# Motor-Z.net
KiCad netlist of a schematic drawn in Altium Designer
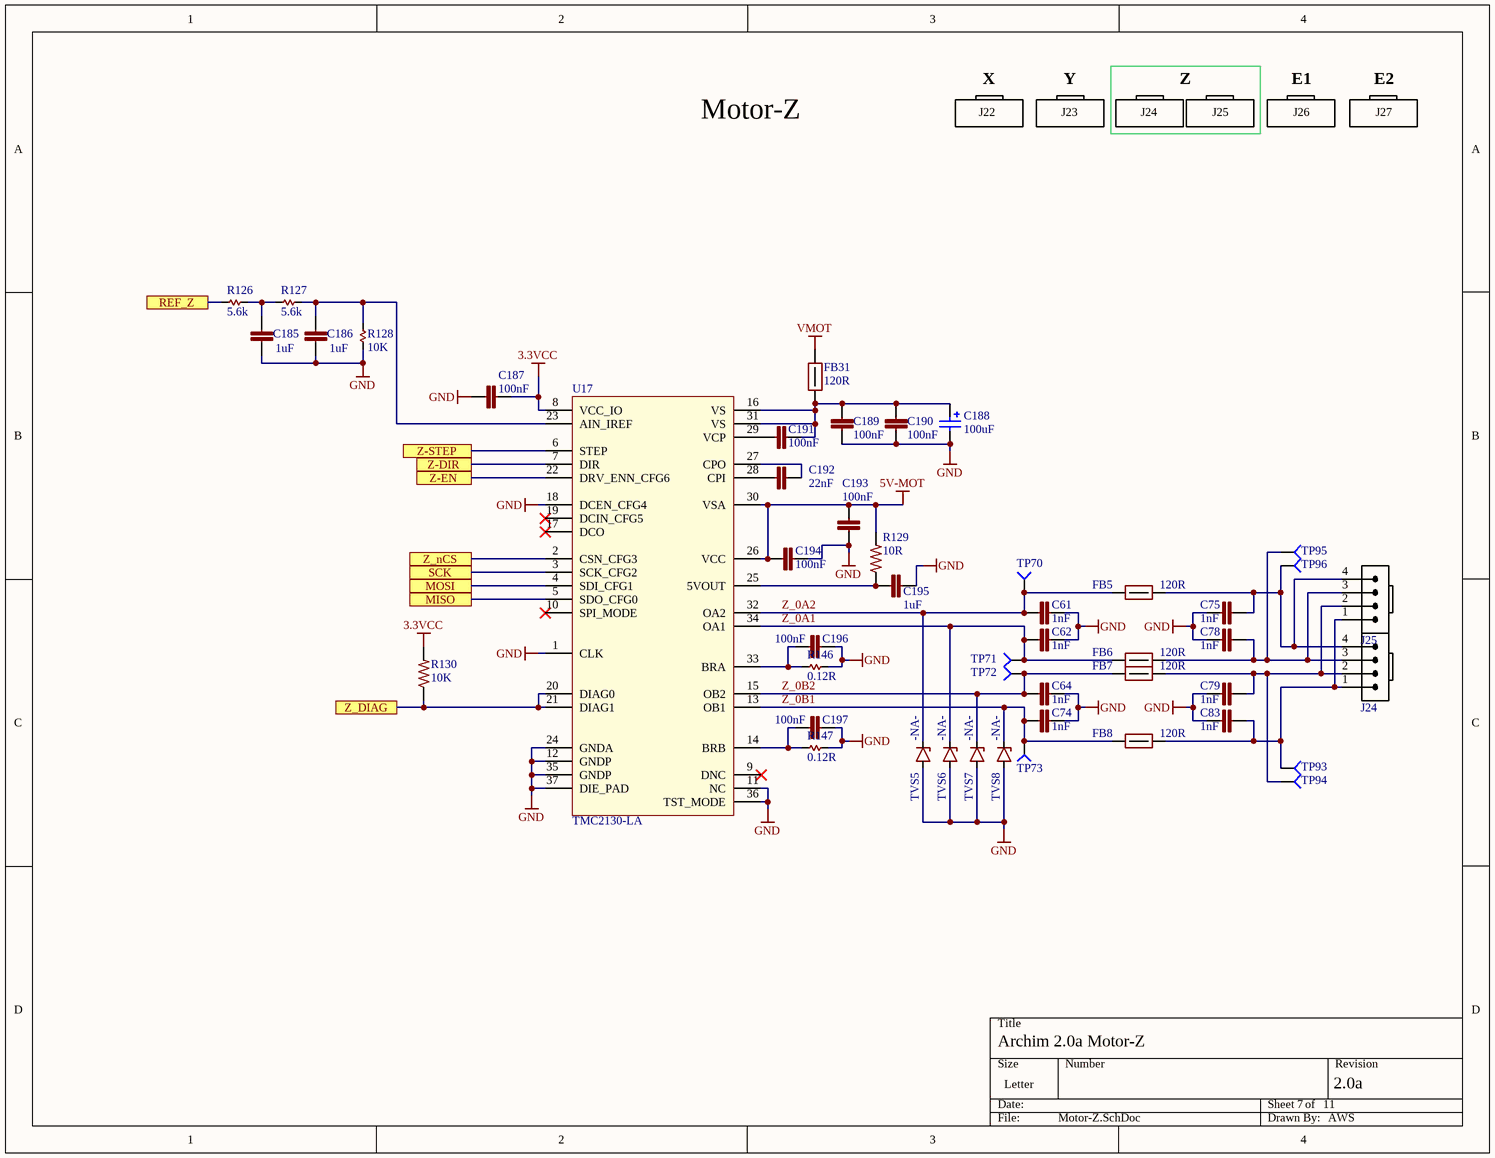
[diagram p0: Motor-Z.SchDoc]

(export (version "E")
  (design (tool "Eeschema 10.0.6"))
  (components
    (comp (ref "C61")
      (value "1nF")
      (footprint "C0402")
      (description "1000pF 50V Ceramic Capacitor X7R 0402 (1005 Metric) 0.039\" L x 0.020\" W (1.00mm x 0.50mm)")
      (fields (field (name "MANUFACTURER") "Murata") (field (name "PART") "1nF 50V X7R 0402"))
      (libsource (lib "3Delight") (part "CAP 1nF 50V 0402 X7R"))
    )
    (comp (ref "C62")
      (value "1nF")
      (footprint "C0402")
      (description "1000pF 50V Ceramic Capacitor X7R 0402 (1005 Metric) 0.039\" L x 0.020\" W (1.00mm x 0.50mm)")
      (fields (field (name "MANUFACTURER") "Murata") (field (name "PART") "1nF 50V X7R 0402"))
      (libsource (lib "3Delight") (part "CAP 1nF 50V 0402 X7R"))
    )
    (comp (ref "C64")
      (value "1nF")
      (footprint "C0402")
      (description "1000pF 50V Ceramic Capacitor X7R 0402 (1005 Metric) 0.039\" L x 0.020\" W (1.00mm x 0.50mm)")
      (fields (field (name "MANUFACTURER") "Murata") (field (name "PART") "1nF 50V X7R 0402"))
      (libsource (lib "3Delight") (part "CAP 1nF 50V 0402 X7R"))
    )
    (comp (ref "C74")
      (value "1nF")
      (footprint "C0402")
      (description "1000pF 50V Ceramic Capacitor X7R 0402 (1005 Metric) 0.039\" L x 0.020\" W (1.00mm x 0.50mm)")
      (fields (field (name "MANUFACTURER") "Murata") (field (name "PART") "1nF 50V X7R 0402"))
      (libsource (lib "3Delight") (part "CAP 1nF 50V 0402 X7R"))
    )
    (comp (ref "C75")
      (value "1nF")
      (footprint "C0402")
      (description "1000pF 50V Ceramic Capacitor X7R 0402 (1005 Metric) 0.039\" L x 0.020\" W (1.00mm x 0.50mm)")
      (fields (field (name "MANUFACTURER") "Murata") (field (name "PART") "1nF 50V X7R 0402"))
      (libsource (lib "3Delight") (part "CAP 1nF 50V 0402 X7R"))
    )
    (comp (ref "C78")
      (value "1nF")
      (footprint "C0402")
      (description "1000pF 50V Ceramic Capacitor X7R 0402 (1005 Metric) 0.039\" L x 0.020\" W (1.00mm x 0.50mm)")
      (fields (field (name "MANUFACTURER") "Murata") (field (name "PART") "1nF 50V X7R 0402"))
      (libsource (lib "3Delight") (part "CAP 1nF 50V 0402 X7R"))
    )
    (comp (ref "C79")
      (value "1nF")
      (footprint "C0402")
      (description "1000pF 50V Ceramic Capacitor X7R 0402 (1005 Metric) 0.039\" L x 0.020\" W (1.00mm x 0.50mm)")
      (fields (field (name "MANUFACTURER") "Murata") (field (name "PART") "1nF 50V X7R 0402"))
      (libsource (lib "3Delight") (part "CAP 1nF 50V 0402 X7R"))
    )
    (comp (ref "C83")
      (value "1nF")
      (footprint "C0402")
      (description "1000pF 50V Ceramic Capacitor X7R 0402 (1005 Metric) 0.039\" L x 0.020\" W (1.00mm x 0.50mm)")
      (fields (field (name "MANUFACTURER") "Murata") (field (name "PART") "1nF 50V X7R 0402"))
      (libsource (lib "3Delight") (part "CAP 1nF 50V 0402 X7R"))
    )
    (comp (ref "C185")
      (value "1uF")
      (footprint "C0402")
      (description "CAP CER 0402 1uF 6.3V 10% X5R")
      (fields (field (name "MANUFACTURER") "Murata") (field (name "PART") "1uF 6.3V X5R 0402"))
      (libsource (lib "") (part "GRM155R60J105KE19D_1"))
    )
    (comp (ref "C186")
      (value "1uF")
      (footprint "C0402")
      (description "CAP CER 0402 1uF 6.3V 10% X5R")
      (fields (field (name "MANUFACTURER") "Murata") (field (name "PART") "1uF 6.3V X5R 0402"))
      (libsource (lib "") (part "GRM155R60J105KE19D_1"))
    )
    (comp (ref "C187")
      (value "100nF")
      (footprint "C0402")
      (description "CAP CER 0402 100nF 16V 10% X7R")
      (fields (field (name "MANUFACTURER") "Murata") (field (name "PART") "0.1uF 16V X7R 0402"))
      (libsource (lib "") (part "GRM155R71C104KA88D_1"))
    )
    (comp (ref "C188")
      (value "100uF")
      (footprint "CAP-ELEC-063063077")
      (description "CAP ALUM 100UF 35V 20% SMD")
      (fields (field (name "MANUFACTURER") "Nichicon") (field (name "PART") "100uF 35V SMD Al-El"))
      (libsource (lib "3Delight") (part "UWT1V101MCL1GS"))
    )
    (comp (ref "C189")
      (value "100nF")
      (footprint "C0603")
      (description "CAP CER 0603 100nF 50V 10% X7R")
      (fields (field (name "MANUFACTURER") "Kemet") (field (name "PART") "100nF 50V X7R 0603"))
      (libsource (lib "") (part "C0603C104K5RACTU_2"))
    )
    (comp (ref "C190")
      (value "100nF")
      (footprint "C0603")
      (description "CAP CER 0603 100nF 50V 10% X7R")
      (fields (field (name "MANUFACTURER") "Kemet") (field (name "PART") "100nF 50V X7R 0603"))
      (libsource (lib "") (part "C0603C104K5RACTU_2"))
    )
    (comp (ref "C191")
      (value "100nF")
      (footprint "C0603")
      (description "CAP CER 0603 100nF 50V 10% X7R")
      (fields (field (name "MANUFACTURER") "Kemet") (field (name "PART") "100nF 50V X7R 0603"))
      (libsource (lib "") (part "C0603C104K5RACTU_1"))
    )
    (comp (ref "C192")
      (value "22nF")
      (footprint "C0402")
      (description "CAP CER 0402 22nF ±10% 50V X7R")
      (fields (field (name "MANUFACTURER") "YAGEO") (field (name "TOLERANCE") "+/- 10%"))
      (libsource (lib "3Delight") (part "GCM155R71H223KA55D"))
    )
    (comp (ref "C193")
      (value "100nF")
      (footprint "C0402")
      (description "CAP CER 0402 100nF 16V 10% X7R")
      (fields (field (name "MANUFACTURER") "Murata") (field (name "PART") "0.1uF 16V X7R 0402"))
      (libsource (lib "3Delight") (part "GRM155R71C104KA88D"))
    )
    (comp (ref "C194")
      (value "100nF")
      (footprint "C0402")
      (description "CAP CER 0402 100nF 16V 10% X7R")
      (fields (field (name "MANUFACTURER") "Murata") (field (name "PART") "0.1uF 16V X7R 0402"))
      (libsource (lib "") (part "GRM155R71C104KA88D_1"))
    )
    (comp (ref "C195")
      (value "1uF")
      (footprint "C0402")
      (description "CAP CER 0402 1uF 6.3V 10% X5R")
      (fields (field (name "MANUFACTURER") "Murata") (field (name "PART") "1uF 6.3V X5R 0402"))
      (libsource (lib "3Delight") (part "GRM155R60J105KE19D"))
    )
    (comp (ref "C196")
      (value "100nF")
      (footprint "C0603")
      (description "CAP CER 0603 100nF 50V 10% X7R")
      (fields (field (name "MANUFACTURER") "Kemet") (field (name "PART") "100nF 50V X7R 0603"))
      (libsource (lib "3Delight") (part "C0603C104K5RACTU"))
    )
    (comp (ref "C197")
      (value "100nF")
      (footprint "C0603")
      (description "CAP CER 0603 100nF 50V 10% X7R")
      (fields (field (name "MANUFACTURER") "Kemet") (field (name "PART") "100nF 50V X7R 0603"))
      (libsource (lib "3Delight") (part "C0603C104K5RACTU"))
    )
    (comp (ref "FB5")
      (value "120R")
      (footprint "FB0603")
      (description "FERRITE BEAD 120 OHM 0603 1LN")
      (fields (field (name "MANUFACTURER") "Samsung") (field (name "PART") "FERRITE 120R 3A 0603"))
      (libsource (lib "3Delight") (part "FERRITE 220R 2.5A 0603"))
    )
    (comp (ref "FB6")
      (value "120R")
      (footprint "FB0603")
      (description "FERRITE BEAD 120 OHM 0603 1LN")
      (fields (field (name "MANUFACTURER") "Samsung") (field (name "PART") "FERRITE 120R 3A 0603"))
      (libsource (lib "3Delight") (part "FERRITE 220R 2.5A 0603"))
    )
    (comp (ref "FB7")
      (value "120R")
      (footprint "FB0603")
      (description "FERRITE BEAD 120 OHM 0603 1LN")
      (fields (field (name "MANUFACTURER") "Samsung") (field (name "PART") "FERRITE 120R 3A 0603"))
      (libsource (lib "3Delight") (part "FERRITE 220R 2.5A 0603"))
    )
    (comp (ref "FB8")
      (value "120R")
      (footprint "FB0603")
      (description "FERRITE BEAD 120 OHM 0603 1LN")
      (fields (field (name "MANUFACTURER") "Samsung") (field (name "PART") "FERRITE 120R 3A 0603"))
      (libsource (lib "3Delight") (part "FERRITE 220R 2.5A 0603"))
    )
    (comp (ref "FB31")
      (value "120R")
      (footprint "FB0603")
      (description "FERRITE BEAD 120 OHM 0603 1LN")
      (fields (field (name "MANUFACTURER") "Samsung") (field (name "PART") "FERRITE 120R 3A 0603"))
      (libsource (lib "Inductors") (part "FERRITE 120R 3A 0603"))
    )
    (comp (ref "J24")
      (value "Molex 0705430038")
      (footprint "4POL254 PIN-IN-PASTE")
      (description "Molex 4 Pin Clip Connector - Pin In Paste footprint")
      (libsource (lib "Connectors") (part "Molex 0705430003 PIP"))
    )
    (comp (ref "J25")
      (value "Molex 0705430038")
      (footprint "4POL254 PIN-IN-PASTE")
      (description "Molex 4 Pin Clip Connector - Pin In Paste footprint")
      (libsource (lib "Connectors") (part "Molex 0705430003 PIP"))
    )
    (comp (ref "R126")
      (value "5.6k")
      (footprint "R0402")
      (description "RES SMD 5.6K OHM 1% 1/16W 0402")
      (fields (field (name "MANUFACTURER") "YAGEO") (field (name "TOLERANCE") "1%"))
      (libsource (lib "Resistors") (part "5.6k 1% 0402"))
    )
    (comp (ref "R127")
      (value "5.6k")
      (footprint "R0402")
      (description "RES SMD 5.6K OHM 1% 1/16W 0402")
      (fields (field (name "MANUFACTURER") "YAGEO") (field (name "TOLERANCE") "1%"))
      (libsource (lib "Resistors") (part "5.6k 1% 0402"))
    )
    (comp (ref "R128")
      (value "10K")
      (footprint "R0402")
      (description "RES SMD 10K OHM 1% 1/16W 0402")
      (fields (field (name "MANUFACTURER") "Yageo") (field (name "PART") "10k 1% 0402"))
      (libsource (lib "Resistors") (part "10k 1% 0402"))
    )
    (comp (ref "R129")
      (value "10R")
      (footprint "R0402")
      (description "RES SMD 10 OHM 1% 1/16W 0402")
      (fields (field (name "MANUFACTURER") "Yageo") (field (name "TOLERANCE") "1%"))
      (libsource (lib "3Delight") (part "RC0402FR-0710RL"))
    )
    (comp (ref "R130")
      (value "10K")
      (footprint "R0402")
      (description "RES SMD 10K OHM 1% 1/16W 0402")
      (fields (field (name "MANUFACTURER") "Yageo") (field (name "PART") "10k 1% 0402"))
      (libsource (lib "3Delight") (part "RC0402FR-0710KP"))
    )
    (comp (ref "R146")
      (value "0.12R")
      (footprint "R1206")
      (description "RES 0.12 OHM 1% 1/2W 1206")
      (fields (field (name "TOLERANCE") "+/- 1%"))
      (libsource (lib "Resistors") (part "0.12R 1% 1206"))
    )
    (comp (ref "R147")
      (value "0.12R")
      (footprint "R1206")
      (description "RES 0.12 OHM 1% 1/2W 1206")
      (fields (field (name "TOLERANCE") "+/- 1%"))
      (libsource (lib "Resistors") (part "0.12R 1% 1206"))
    )
    (comp (ref "TP70")
      (value "TP4")
      (footprint "TP-2")
      (description "Socket")
      (libsource (lib "Archim") (part "Socket"))
    )
    (comp (ref "TP71")
      (value "TP4")
      (footprint "TP-2")
      (description "Socket")
      (libsource (lib "Archim") (part "Socket"))
    )
    (comp (ref "TP72")
      (value "TP4")
      (footprint "TP-2")
      (description "Socket")
      (libsource (lib "Archim") (part "Socket"))
    )
    (comp (ref "TP73")
      (value "TP4")
      (footprint "TP-2")
      (description "Socket")
      (libsource (lib "Archim") (part "Socket"))
    )
    (comp (ref "TP93")
      (value "TP4")
      (footprint "TP-2")
      (description "Socket")
      (libsource (lib "Archim") (part "Socket"))
    )
    (comp (ref "TP94")
      (value "TP4")
      (footprint "TP-2")
      (description "Socket")
      (libsource (lib "Archim") (part "Socket"))
    )
    (comp (ref "TP95")
      (value "TP4")
      (footprint "TP-2")
      (description "Socket")
      (libsource (lib "Archim") (part "Socket"))
    )
    (comp (ref "TP96")
      (value "TP4")
      (footprint "TP-2")
      (description "Socket")
      (libsource (lib "Archim") (part "Socket"))
    )
    (comp (ref "TVS5")
      (value "-NA-")
      (footprint "SMF")
      (description "TVS DIODE 30VWM 48.4VC SMF")
      (fields (field (name "MANUFACTURER") "Vishay") (field (name "PART") "TVS Diode 48.4VC"))
      (libsource (lib "3Delight") (part "TVS 30V SMF"))
    )
    (comp (ref "TVS6")
      (value "-NA-")
      (footprint "SMF")
      (description "TVS DIODE 30VWM 48.4VC SMF")
      (fields (field (name "MANUFACTURER") "Vishay") (field (name "PART") "TVS Diode 48.4VC"))
      (libsource (lib "3Delight") (part "TVS 30V SMF"))
    )
    (comp (ref "TVS7")
      (value "-NA-")
      (footprint "SMF")
      (description "TVS DIODE 30VWM 48.4VC SMF")
      (fields (field (name "MANUFACTURER") "Vishay") (field (name "PART") "TVS Diode 48.4VC"))
      (libsource (lib "3Delight") (part "TVS 30V SMF"))
    )
    (comp (ref "TVS8")
      (value "-NA-")
      (footprint "SMF")
      (description "TVS DIODE 30VWM 48.4VC SMF")
      (fields (field (name "MANUFACTURER") "Vishay") (field (name "PART") "TVS Diode 48.4VC"))
      (libsource (lib "3Delight") (part "TVS 30V SMF"))
    )
    (comp (ref "U17")
      (value "TMC2130-LA")
      (footprint "QFN36-50P500X600X900_HS-37N")
      (description "IC STEPPER MOTOR DVR SPI 36QFN")
      (fields (field (name "MANUFACTURER") "Trinamic") (field (name "PART") "TMC2130"))
      (libsource (lib "ICs-Motor Controller") (part "TMC2130-LA-T"))
    )
  )
  (nets
    (net (code "1") (name "/MISO") (class "Default")
      (node (ref "U17") (pin "5") (pinfunction "SDO_CFG0_5") (pintype "passive"))
    )
    (net (code "2") (name "/MOSI") (class "Default")
      (node (ref "U17") (pin "4") (pinfunction "SDI_CFG1_4") (pintype "passive"))
    )
    (net (code "3") (name "/REF_Z") (class "Default")
      (node (ref "R126") (pin "1") (pinfunction "1_1") (pintype "passive"))
    )
    (net (code "4") (name "/SCK") (class "Default")
      (node (ref "U17") (pin "3") (pinfunction "SCK_CFG2_3") (pintype "passive"))
    )
    (net (code "5") (name "/Z-DIR") (class "Default")
      (node (ref "U17") (pin "7") (pinfunction "DIR_7") (pintype "passive"))
    )
    (net (code "6") (name "/Z-EN") (class "Default")
      (node (ref "U17") (pin "22") (pinfunction "DRV_ENN_CFG6_22") (pintype "passive"))
    )
    (net (code "7") (name "/Z-STEP") (class "Default")
      (node (ref "U17") (pin "6") (pinfunction "STEP_6") (pintype "passive"))
    )
    (net (code "8") (name "/Z_0A1") (class "Default")
      (node (ref "C62") (pin "1") (pinfunction "1_1") (pintype "passive"))
      (node (ref "FB6") (pin "1") (pinfunction "1_1") (pintype "passive"))
      (node (ref "TP71") (pin "1") (pinfunction "1_1") (pintype "passive"))
      (node (ref "TVS6") (pin "K") (pinfunction "K_K") (pintype "passive"))
      (node (ref "U17") (pin "34") (pinfunction "OA1_34") (pintype "passive"))
    )
    (net (code "9") (name "/Z_0A2") (class "Default")
      (node (ref "C61") (pin "1") (pinfunction "1_1") (pintype "passive"))
      (node (ref "FB5") (pin "1") (pinfunction "1_1") (pintype "passive"))
      (node (ref "TP70") (pin "1") (pinfunction "1_1") (pintype "passive"))
      (node (ref "TVS5") (pin "K") (pinfunction "K_K") (pintype "passive"))
      (node (ref "U17") (pin "32") (pinfunction "OA2_32") (pintype "passive"))
    )
    (net (code "10") (name "/Z_0B1") (class "Default")
      (node (ref "C74") (pin "1") (pinfunction "1_1") (pintype "passive"))
      (node (ref "FB8") (pin "1") (pinfunction "1_1") (pintype "passive"))
      (node (ref "TP73") (pin "1") (pinfunction "1_1") (pintype "passive"))
      (node (ref "TVS8") (pin "K") (pinfunction "K_K") (pintype "passive"))
      (node (ref "U17") (pin "13") (pinfunction "OB1_13") (pintype "passive"))
    )
    (net (code "11") (name "/Z_0B2") (class "Default")
      (node (ref "C64") (pin "1") (pinfunction "1_1") (pintype "passive"))
      (node (ref "FB7") (pin "1") (pinfunction "1_1") (pintype "passive"))
      (node (ref "TP72") (pin "1") (pinfunction "1_1") (pintype "passive"))
      (node (ref "TVS7") (pin "K") (pinfunction "K_K") (pintype "passive"))
      (node (ref "U17") (pin "15") (pinfunction "OB2_15") (pintype "passive"))
    )
    (net (code "12") (name "/Z_DIAG") (class "Default")
      (node (ref "R130") (pin "1") (pinfunction "1_1") (pintype "passive"))
      (node (ref "U17") (pin "20") (pinfunction "DIAG0_20") (pintype "passive"))
      (node (ref "U17") (pin "21") (pinfunction "DIAG1_21") (pintype "passive"))
    )
    (net (code "13") (name "/Z_nCS") (class "Default")
      (node (ref "U17") (pin "2") (pinfunction "CSN_CFG3_2") (pintype "passive"))
    )
    (net (code "14") (name "3.3VCC") (class "Default")
      (node (ref "C187") (pin "1") (pinfunction "1_1") (pintype "passive"))
      (node (ref "R130") (pin "2") (pinfunction "2_2") (pintype "passive"))
      (node (ref "U17") (pin "8") (pinfunction "VCC_IO_8") (pintype "passive"))
    )
    (net (code "15") (name "5V-MOT") (class "Default")
      (node (ref "C193") (pin "2") (pinfunction "2_2") (pintype "passive"))
      (node (ref "C194") (pin "2") (pinfunction "2_2") (pintype "passive"))
      (node (ref "R129") (pin "2") (pinfunction "2_2") (pintype "passive"))
      (node (ref "U17") (pin "26") (pinfunction "VCC_26") (pintype "passive"))
      (node (ref "U17") (pin "30") (pinfunction "VSA_30") (pintype "passive"))
    )
    (net (code "16") (name "GND") (class "Default")
      (node (ref "C185") (pin "2") (pinfunction "2_2") (pintype "passive"))
      (node (ref "C186") (pin "2") (pinfunction "2_2") (pintype "passive"))
      (node (ref "C187") (pin "2") (pinfunction "2_2") (pintype "passive"))
      (node (ref "C188") (pin "2") (pinfunction "2_2") (pintype "passive"))
      (node (ref "C189") (pin "1") (pinfunction "1_1") (pintype "passive"))
      (node (ref "C190") (pin "1") (pinfunction "1_1") (pintype "passive"))
      (node (ref "C193") (pin "1") (pinfunction "1_1") (pintype "passive"))
      (node (ref "C194") (pin "1") (pinfunction "1_1") (pintype "passive"))
      (node (ref "C195") (pin "2") (pinfunction "2_2") (pintype "passive"))
      (node (ref "C196") (pin "1") (pinfunction "1_1") (pintype "passive"))
      (node (ref "C197") (pin "1") (pinfunction "1_1") (pintype "passive"))
      (node (ref "C61") (pin "2") (pinfunction "2_2") (pintype "passive"))
      (node (ref "C62") (pin "2") (pinfunction "2_2") (pintype "passive"))
      (node (ref "C64") (pin "2") (pinfunction "2_2") (pintype "passive"))
      (node (ref "C74") (pin "2") (pinfunction "2_2") (pintype "passive"))
      (node (ref "C75") (pin "1") (pinfunction "1_1") (pintype "passive"))
      (node (ref "C78") (pin "1") (pinfunction "1_1") (pintype "passive"))
      (node (ref "C79") (pin "1") (pinfunction "1_1") (pintype "passive"))
      (node (ref "C83") (pin "1") (pinfunction "1_1") (pintype "passive"))
      (node (ref "R128") (pin "1") (pinfunction "1_1") (pintype "passive"))
      (node (ref "R146") (pin "2") (pinfunction "2_2") (pintype "passive"))
      (node (ref "R147") (pin "2") (pinfunction "2_2") (pintype "passive"))
      (node (ref "TVS5") (pin "A") (pinfunction "A_A") (pintype "passive"))
      (node (ref "TVS6") (pin "A") (pinfunction "A_A") (pintype "passive"))
      (node (ref "TVS7") (pin "A") (pinfunction "A_A") (pintype "passive"))
      (node (ref "TVS8") (pin "A") (pinfunction "A_A") (pintype "passive"))
      (node (ref "U17") (pin "1") (pinfunction "CLK_1") (pintype "passive"))
      (node (ref "U17") (pin "11") (pinfunction "NC_11") (pintype "passive"))
      (node (ref "U17") (pin "12") (pinfunction "GNDP_12") (pintype "passive"))
      (node (ref "U17") (pin "18") (pinfunction "DCEN_CFG4_18") (pintype "passive"))
      (node (ref "U17") (pin "24") (pinfunction "GNDA_24") (pintype "passive"))
      (node (ref "U17") (pin "35") (pinfunction "GNDP_35") (pintype "passive"))
      (node (ref "U17") (pin "36") (pinfunction "TST_MODE_36") (pintype "passive"))
      (node (ref "U17") (pin "37") (pinfunction "DIE_PAD_37") (pintype "passive"))
    )
    (net (code "17") (name "Net-(C75-Pad2)") (class "Default")
      (node (ref "C75") (pin "2") (pinfunction "2_2") (pintype "passive"))
      (node (ref "FB5") (pin "2") (pinfunction "2_2") (pintype "passive"))
      (node (ref "J24") (pin "4") (pinfunction "4_4") (pintype "passive"))
      (node (ref "J25") (pin "4") (pinfunction "4_4") (pintype "passive"))
      (node (ref "TP96") (pin "1") (pinfunction "1_1") (pintype "passive"))
    )
    (net (code "18") (name "Net-(C78-Pad2)") (class "Default")
      (node (ref "C78") (pin "2") (pinfunction "2_2") (pintype "passive"))
      (node (ref "FB6") (pin "2") (pinfunction "2_2") (pintype "passive"))
      (node (ref "J24") (pin "3") (pinfunction "3_3") (pintype "passive"))
      (node (ref "J25") (pin "3") (pinfunction "3_3") (pintype "passive"))
      (node (ref "TP95") (pin "1") (pinfunction "1_1") (pintype "passive"))
    )
    (net (code "19") (name "Net-(C79-Pad2)") (class "Default")
      (node (ref "C79") (pin "2") (pinfunction "2_2") (pintype "passive"))
      (node (ref "FB7") (pin "2") (pinfunction "2_2") (pintype "passive"))
      (node (ref "J24") (pin "2") (pinfunction "2_2") (pintype "passive"))
      (node (ref "J25") (pin "2") (pinfunction "2_2") (pintype "passive"))
      (node (ref "TP94") (pin "1") (pinfunction "1_1") (pintype "passive"))
    )
    (net (code "20") (name "Net-(C83-Pad2)") (class "Default")
      (node (ref "C83") (pin "2") (pinfunction "2_2") (pintype "passive"))
      (node (ref "FB8") (pin "2") (pinfunction "2_2") (pintype "passive"))
      (node (ref "J24") (pin "1") (pinfunction "1_1") (pintype "passive"))
      (node (ref "J25") (pin "1") (pinfunction "1_1") (pintype "passive"))
      (node (ref "TP93") (pin "1") (pinfunction "1_1") (pintype "passive"))
    )
    (net (code "21") (name "Net-(C185-Pad1)") (class "Default")
      (node (ref "C185") (pin "1") (pinfunction "1_1") (pintype "passive"))
      (node (ref "R126") (pin "2") (pinfunction "2_2") (pintype "passive"))
      (node (ref "R127") (pin "1") (pinfunction "1_1") (pintype "passive"))
    )
    (net (code "22") (name "Net-(C188-Pad1)") (class "Default")
      (node (ref "C188") (pin "1") (pinfunction "1_1") (pintype "passive"))
      (node (ref "C189") (pin "2") (pinfunction "2_2") (pintype "passive"))
      (node (ref "C190") (pin "2") (pinfunction "2_2") (pintype "passive"))
      (node (ref "C191") (pin "2") (pinfunction "2_2") (pintype "passive"))
      (node (ref "FB31") (pin "1") (pinfunction "1_1") (pintype "passive"))
      (node (ref "U17") (pin "16") (pinfunction "VS_16") (pintype "passive"))
      (node (ref "U17") (pin "31") (pinfunction "VS_31") (pintype "passive"))
    )
    (net (code "23") (name "Net-(U17-5VOUT)") (class "Default")
      (node (ref "C195") (pin "1") (pinfunction "1_1") (pintype "passive"))
      (node (ref "R129") (pin "1") (pinfunction "1_1") (pintype "passive"))
      (node (ref "U17") (pin "25") (pinfunction "5VOUT_25") (pintype "passive"))
    )
    (net (code "24") (name "Net-(U17-AIN_IREF)") (class "Default")
      (node (ref "C186") (pin "1") (pinfunction "1_1") (pintype "passive"))
      (node (ref "R127") (pin "2") (pinfunction "2_2") (pintype "passive"))
      (node (ref "R128") (pin "2") (pinfunction "2_2") (pintype "passive"))
      (node (ref "U17") (pin "23") (pinfunction "AIN_IREF_23") (pintype "passive"))
    )
    (net (code "25") (name "Net-(U17-BRA)") (class "Default")
      (node (ref "C196") (pin "2") (pinfunction "2_2") (pintype "passive"))
      (node (ref "R146") (pin "1") (pinfunction "1_1") (pintype "passive"))
      (node (ref "U17") (pin "33") (pinfunction "BRA_33") (pintype "passive"))
    )
    (net (code "26") (name "Net-(U17-BRB)") (class "Default")
      (node (ref "C197") (pin "2") (pinfunction "2_2") (pintype "passive"))
      (node (ref "R147") (pin "1") (pinfunction "1_1") (pintype "passive"))
      (node (ref "U17") (pin "14") (pinfunction "BRB_14") (pintype "passive"))
    )
    (net (code "27") (name "Net-(U17-CPI)") (class "Default")
      (node (ref "C192") (pin "1") (pinfunction "1_1") (pintype "passive"))
      (node (ref "U17") (pin "28") (pinfunction "CPI_28") (pintype "passive"))
    )
    (net (code "28") (name "Net-(U17-CPO)") (class "Default")
      (node (ref "C192") (pin "2") (pinfunction "2_2") (pintype "passive"))
      (node (ref "U17") (pin "27") (pinfunction "CPO_27") (pintype "passive"))
    )
    (net (code "29") (name "Net-(U17-VCP)") (class "Default")
      (node (ref "C191") (pin "1") (pinfunction "1_1") (pintype "passive"))
      (node (ref "U17") (pin "29") (pinfunction "VCP_29") (pintype "passive"))
    )
    (net (code "30") (name "VMOT") (class "Default")
      (node (ref "FB31") (pin "2") (pinfunction "2_2") (pintype "passive"))
    )
    (net (code "31") (name "unconnected-(U17-DCIN_CFG5-Pad19)") (class "Default")
      (node (ref "U17") (pin "19") (pinfunction "DCIN_CFG5_19") (pintype "passive+no_connect"))
    )
    (net (code "32") (name "unconnected-(U17-DCO-Pad17)") (class "Default")
      (node (ref "U17") (pin "17") (pinfunction "DCO_17") (pintype "passive+no_connect"))
    )
    (net (code "33") (name "unconnected-(U17-DNC-Pad9)") (class "Default")
      (node (ref "U17") (pin "9") (pinfunction "DNC_9") (pintype "passive+no_connect"))
    )
    (net (code "34") (name "unconnected-(U17-SPI_MODE-Pad10)") (class "Default")
      (node (ref "U17") (pin "10") (pinfunction "SPI_MODE_10") (pintype "passive+no_connect"))
    )
  )
)
